# Common_slot2.net
KiCad netlist of a schematic drawn in EAGLE
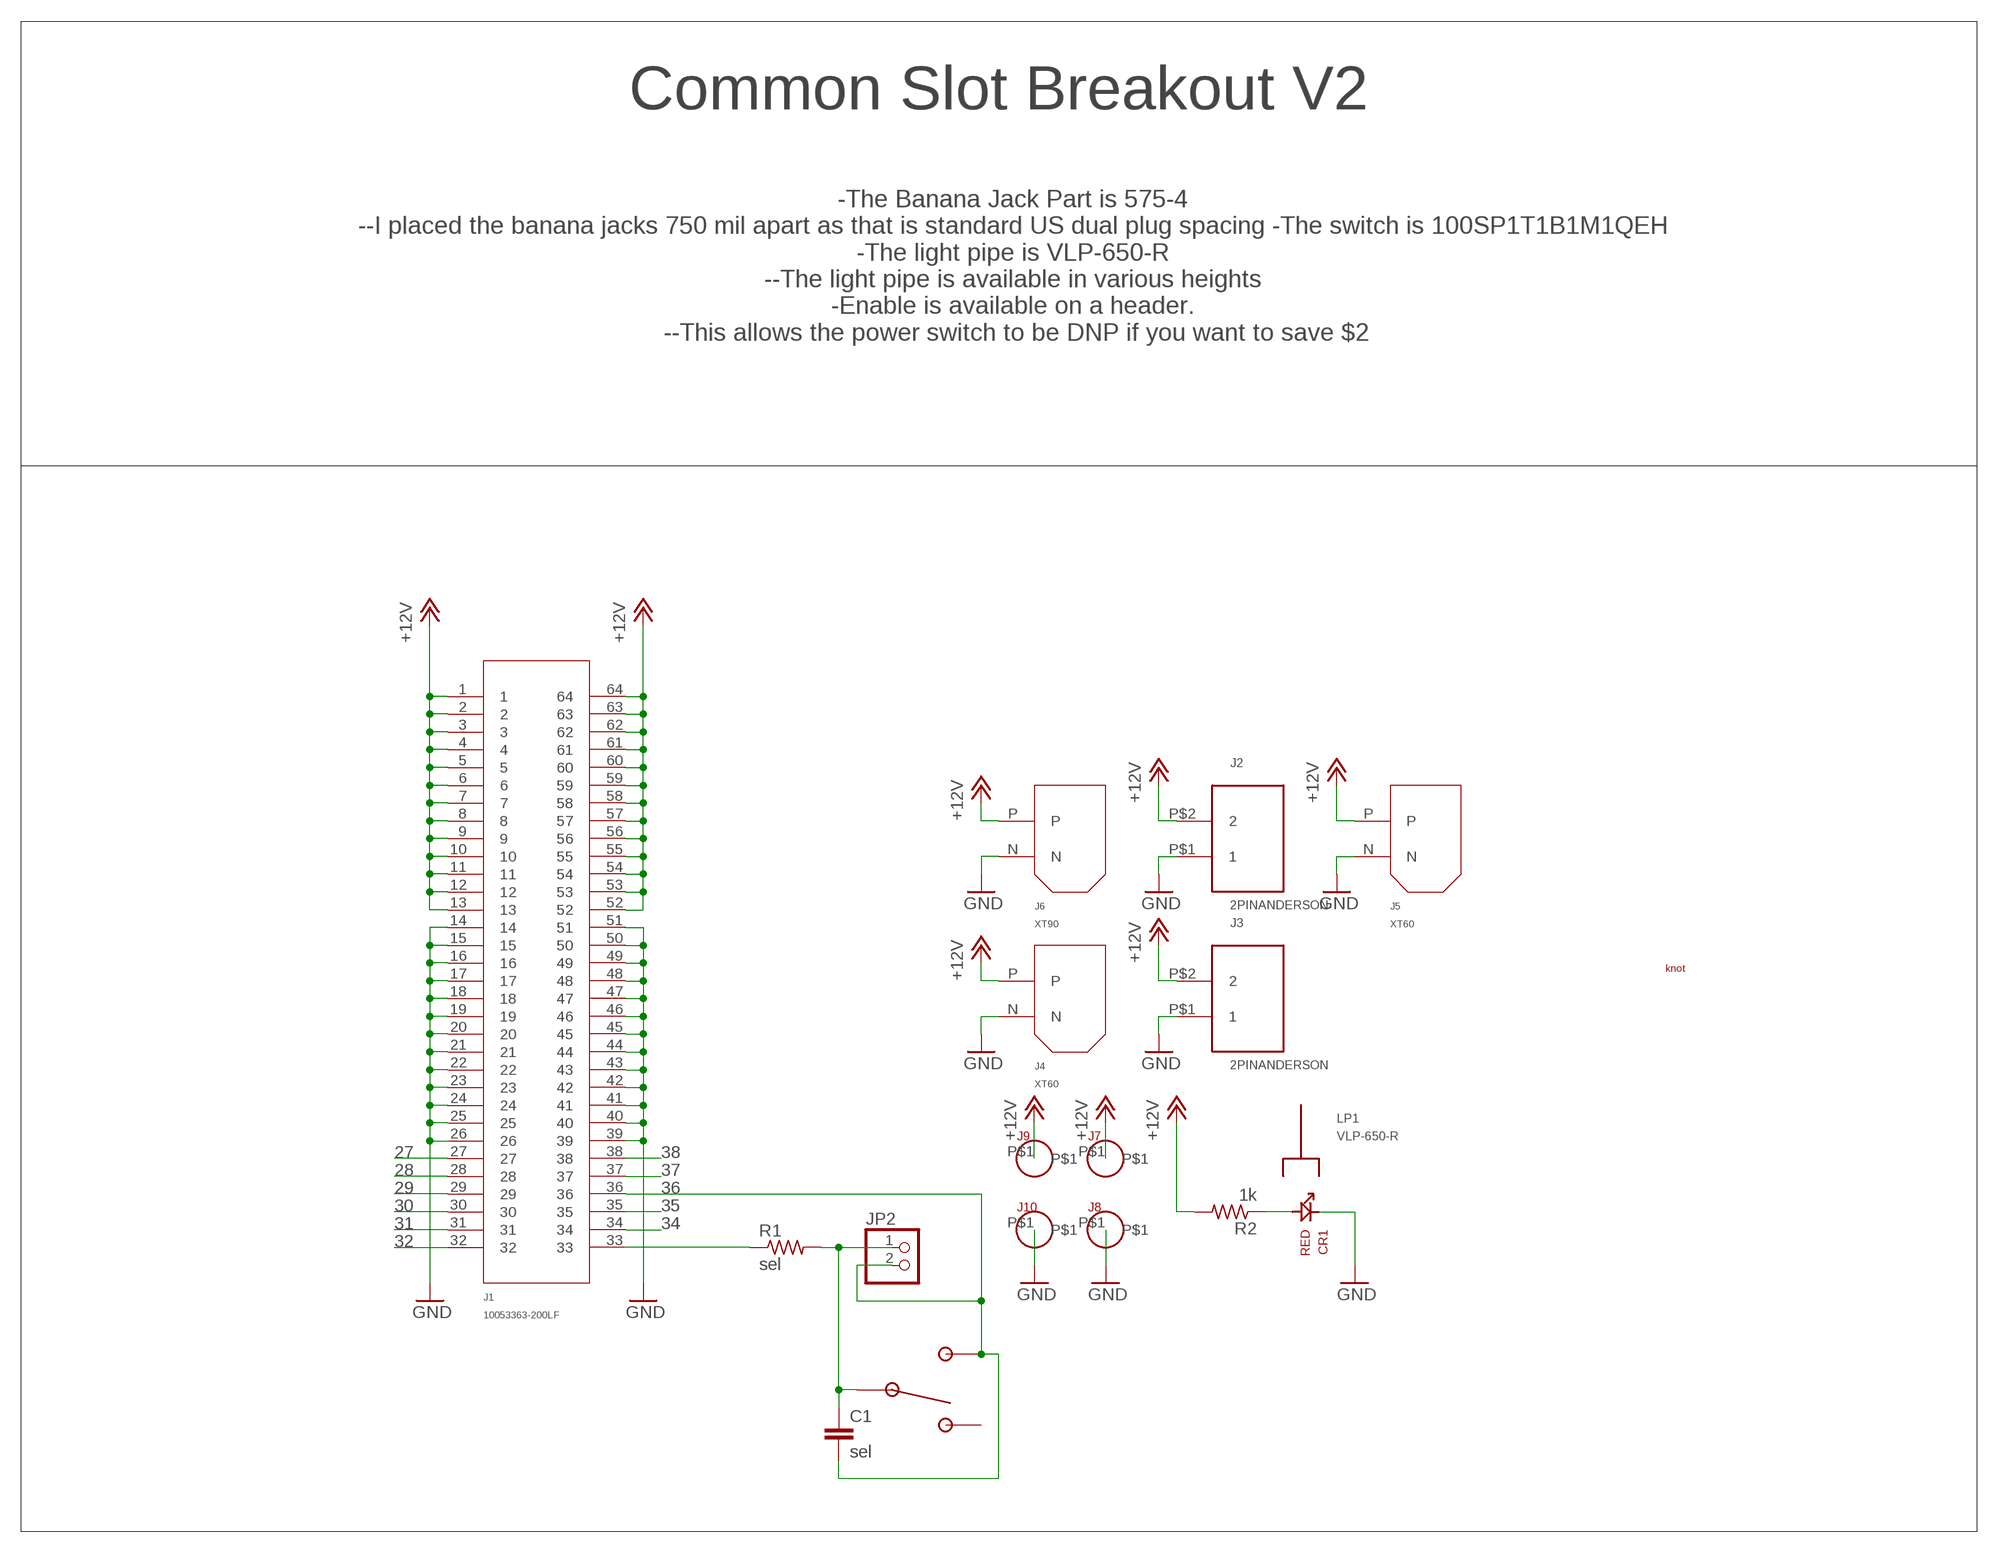
[diagram p0: schematic, sheet 1]

(export (version "E")
  (design (tool "Eeschema 10.0.6"))
  (components
    (comp (ref "C1")
      (value "sel")
      (footprint "eagle-import:0603")
      (libsource (lib "eagle-import") (part "0603_CAPACITOR"))
    )
    (comp (ref "CR1")
      (value "RED")
      (footprint "eagle-import:0603_DIODE")
      (fields (field (name "PARTNO") "732-4978-1-ND"))
      (libsource (lib "eagle-import") (part "150060RS75000"))
    )
    (comp (ref "J1")
      (value "10053363-200LF")
      (footprint "eagle-import:10053363-200LF")
      (fields (field (name "PARTNO") "609-2861-ND"))
      (libsource (lib "eagle-import") (part "10053363-200LF"))
    )
    (comp (ref "J2")
      (value "2PINANDERSON")
      (footprint "eagle-import:APP")
      (libsource (lib "eagle-import") (part "2PINANDERSON"))
    )
    (comp (ref "J3")
      (value "2PINANDERSON")
      (footprint "eagle-import:APP")
      (libsource (lib "eagle-import") (part "2PINANDERSON"))
    )
    (comp (ref "J4")
      (value "XT60")
      (footprint "eagle-import:XT60")
      (libsource (lib "eagle-import") (part "XT60"))
    )
    (comp (ref "J5")
      (value "XT60")
      (footprint "eagle-import:XT60")
      (libsource (lib "eagle-import") (part "XT60"))
    )
    (comp (ref "J6")
      (value "XT90")
      (footprint "eagle-import:XT90")
      (libsource (lib "eagle-import") (part "XT90"))
    )
    (comp (ref "J7")
      (value "BANANA")
      (footprint "eagle-import:BANANA")
      (fields (field (name "PARTNO") "36-575-4-ND"))
      (libsource (lib "eagle-import") (part "BANANA"))
    )
    (comp (ref "J8")
      (value "BANANA")
      (footprint "eagle-import:BANANA")
      (fields (field (name "PARTNO") "36-575-4-ND"))
      (libsource (lib "eagle-import") (part "BANANA"))
    )
    (comp (ref "J9")
      (value "BANANA")
      (footprint "eagle-import:BANANA")
      (fields (field (name "PARTNO") "36-575-4-ND"))
      (libsource (lib "eagle-import") (part "BANANA"))
    )
    (comp (ref "J10")
      (value "BANANA")
      (footprint "eagle-import:BANANA")
      (fields (field (name "PARTNO") "36-575-4-ND"))
      (libsource (lib "eagle-import") (part "BANANA"))
    )
    (comp (ref "JP2")
      (value "PINHD-1X2")
      (footprint "eagle-import:1X02")
      (libsource (lib "eagle-import") (part "PINHD-1X2"))
    )
    (comp (ref "LP1")
      (value "VLP-650-R")
      (footprint "eagle-import:VLP-XXX-R")
      (fields (field (name "PARTNO") "492-2537-ND"))
      (libsource (lib "eagle-import") (part "VLP-650-R"))
    )
    (comp (ref "R1")
      (value "sel")
      (footprint "eagle-import:0603")
      (libsource (lib "eagle-import") (part "0603_RESISTOR"))
    )
    (comp (ref "R2")
      (value "1k")
      (footprint "eagle-import:0603")
      (libsource (lib "eagle-import") (part "0603_RESISTOR"))
    )
    (comp (ref "SW1")
      (value "100SP1T1B1M1QEH")
      (footprint "eagle-import:100SP1T1B1M1QEH")
      (fields (field (name "PARTNO") "EG2350-ND"))
      (libsource (lib "eagle-import") (part "100SP1T1B1M1QEH"))
    )
    (comp (ref "U$1")
      (value "THIEF_FULL")
      (footprint "eagle-import:THIEF_KNOT")
      (fields (field (name "PARTNO") "NA"))
      (libsource (lib "eagle-import") (part "THIEF_FULL"))
    )
  )
  (nets
    (net (code "1") (name "+12V") (class "Default")
      (node (ref "J1") (pin "1") (pinfunction "1_1") (pintype "bidirectional"))
      (node (ref "J1") (pin "10") (pinfunction "10_10") (pintype "bidirectional"))
      (node (ref "J1") (pin "11") (pinfunction "11_11") (pintype "bidirectional"))
      (node (ref "J1") (pin "12") (pinfunction "12_12") (pintype "bidirectional"))
      (node (ref "J1") (pin "13") (pinfunction "13_13") (pintype "bidirectional"))
      (node (ref "J1") (pin "2") (pinfunction "2_2") (pintype "bidirectional"))
      (node (ref "J1") (pin "3") (pinfunction "3_3") (pintype "bidirectional"))
      (node (ref "J1") (pin "4") (pinfunction "4_4") (pintype "bidirectional"))
      (node (ref "J1") (pin "5") (pinfunction "5_5") (pintype "bidirectional"))
      (node (ref "J1") (pin "52") (pinfunction "52_52") (pintype "bidirectional"))
      (node (ref "J1") (pin "53") (pinfunction "53_53") (pintype "bidirectional"))
      (node (ref "J1") (pin "54") (pinfunction "54_54") (pintype "bidirectional"))
      (node (ref "J1") (pin "55") (pinfunction "55_55") (pintype "bidirectional"))
      (node (ref "J1") (pin "56") (pinfunction "56_56") (pintype "bidirectional"))
      (node (ref "J1") (pin "57") (pinfunction "57_57") (pintype "bidirectional"))
      (node (ref "J1") (pin "58") (pinfunction "58_58") (pintype "bidirectional"))
      (node (ref "J1") (pin "59") (pinfunction "59_59") (pintype "bidirectional"))
      (node (ref "J1") (pin "6") (pinfunction "6_6") (pintype "bidirectional"))
      (node (ref "J1") (pin "60") (pinfunction "60_60") (pintype "bidirectional"))
      (node (ref "J1") (pin "61") (pinfunction "61_61") (pintype "bidirectional"))
      (node (ref "J1") (pin "62") (pinfunction "62_62") (pintype "bidirectional"))
      (node (ref "J1") (pin "63") (pinfunction "63_63") (pintype "bidirectional"))
      (node (ref "J1") (pin "64") (pinfunction "64_64") (pintype "bidirectional"))
      (node (ref "J1") (pin "7") (pinfunction "7_7") (pintype "bidirectional"))
      (node (ref "J1") (pin "8") (pinfunction "8_8") (pintype "bidirectional"))
      (node (ref "J1") (pin "9") (pinfunction "9_9") (pintype "bidirectional"))
      (node (ref "J2") (pin "P$2") (pinfunction "2_P$2") (pintype "bidirectional"))
      (node (ref "J3") (pin "P$2") (pinfunction "2_P$2") (pintype "bidirectional"))
      (node (ref "J4") (pin "P") (pinfunction "P_P") (pintype "bidirectional"))
      (node (ref "J5") (pin "P") (pinfunction "P_P") (pintype "bidirectional"))
      (node (ref "J6") (pin "P") (pinfunction "P_P") (pintype "bidirectional"))
      (node (ref "J7") (pin "P$1") (pinfunction "P$1_P$1") (pintype "bidirectional"))
      (node (ref "J9") (pin "P$1") (pinfunction "P$1_P$1") (pintype "bidirectional"))
      (node (ref "R2") (pin "2") (pinfunction "2_2") (pintype "passive"))
    )
    (net (code "2") (name "/27") (class "Default")
      (node (ref "J1") (pin "27") (pinfunction "27_27") (pintype "bidirectional"))
    )
    (net (code "3") (name "/28") (class "Default")
      (node (ref "J1") (pin "28") (pinfunction "28_28") (pintype "bidirectional"))
    )
    (net (code "4") (name "/29") (class "Default")
      (node (ref "J1") (pin "29") (pinfunction "29_29") (pintype "bidirectional"))
    )
    (net (code "5") (name "/30") (class "Default")
      (node (ref "J1") (pin "30") (pinfunction "30_30") (pintype "bidirectional"))
    )
    (net (code "6") (name "/31") (class "Default")
      (node (ref "J1") (pin "31") (pinfunction "31_31") (pintype "bidirectional"))
    )
    (net (code "7") (name "/32") (class "Default")
      (node (ref "J1") (pin "32") (pinfunction "32_32") (pintype "bidirectional"))
    )
    (net (code "8") (name "/34") (class "Default")
      (node (ref "J1") (pin "34") (pinfunction "34_34") (pintype "bidirectional"))
    )
    (net (code "9") (name "/35") (class "Default")
      (node (ref "J1") (pin "35") (pinfunction "35_35") (pintype "bidirectional"))
    )
    (net (code "10") (name "/36") (class "Default")
      (node (ref "C1") (pin "2") (pinfunction "2_2") (pintype "passive"))
      (node (ref "J1") (pin "36") (pinfunction "36_36") (pintype "bidirectional"))
      (node (ref "JP2") (pin "2") (pinfunction "2_2") (pintype "passive"))
      (node (ref "SW1") (pin "2") (pinfunction "P$2_2") (pintype "bidirectional"))
    )
    (net (code "11") (name "/37") (class "Default")
      (node (ref "J1") (pin "37") (pinfunction "37_37") (pintype "bidirectional"))
    )
    (net (code "12") (name "/38") (class "Default")
      (node (ref "J1") (pin "38") (pinfunction "38_38") (pintype "bidirectional"))
    )
    (net (code "13") (name "GND") (class "Default")
      (node (ref "CR1") (pin "K") (pinfunction "K_K") (pintype "bidirectional"))
      (node (ref "J1") (pin "14") (pinfunction "14_14") (pintype "bidirectional"))
      (node (ref "J1") (pin "15") (pinfunction "15_15") (pintype "bidirectional"))
      (node (ref "J1") (pin "16") (pinfunction "16_16") (pintype "bidirectional"))
      (node (ref "J1") (pin "17") (pinfunction "17_17") (pintype "bidirectional"))
      (node (ref "J1") (pin "18") (pinfunction "18_18") (pintype "bidirectional"))
      (node (ref "J1") (pin "19") (pinfunction "19_19") (pintype "bidirectional"))
      (node (ref "J1") (pin "20") (pinfunction "20_20") (pintype "bidirectional"))
      (node (ref "J1") (pin "21") (pinfunction "21_21") (pintype "bidirectional"))
      (node (ref "J1") (pin "22") (pinfunction "22_22") (pintype "bidirectional"))
      (node (ref "J1") (pin "23") (pinfunction "23_23") (pintype "bidirectional"))
      (node (ref "J1") (pin "24") (pinfunction "24_24") (pintype "bidirectional"))
      (node (ref "J1") (pin "25") (pinfunction "25_25") (pintype "bidirectional"))
      (node (ref "J1") (pin "26") (pinfunction "26_26") (pintype "bidirectional"))
      (node (ref "J1") (pin "39") (pinfunction "39_39") (pintype "bidirectional"))
      (node (ref "J1") (pin "40") (pinfunction "40_40") (pintype "bidirectional"))
      (node (ref "J1") (pin "41") (pinfunction "41_41") (pintype "bidirectional"))
      (node (ref "J1") (pin "42") (pinfunction "42_42") (pintype "bidirectional"))
      (node (ref "J1") (pin "43") (pinfunction "43_43") (pintype "bidirectional"))
      (node (ref "J1") (pin "44") (pinfunction "44_44") (pintype "bidirectional"))
      (node (ref "J1") (pin "45") (pinfunction "45_45") (pintype "bidirectional"))
      (node (ref "J1") (pin "46") (pinfunction "46_46") (pintype "bidirectional"))
      (node (ref "J1") (pin "47") (pinfunction "47_47") (pintype "bidirectional"))
      (node (ref "J1") (pin "48") (pinfunction "48_48") (pintype "bidirectional"))
      (node (ref "J1") (pin "49") (pinfunction "49_49") (pintype "bidirectional"))
      (node (ref "J1") (pin "50") (pinfunction "50_50") (pintype "bidirectional"))
      (node (ref "J1") (pin "51") (pinfunction "51_51") (pintype "bidirectional"))
      (node (ref "J10") (pin "P$1") (pinfunction "P$1_P$1") (pintype "bidirectional"))
      (node (ref "J2") (pin "P$1") (pinfunction "1_P$1") (pintype "bidirectional"))
      (node (ref "J3") (pin "P$1") (pinfunction "1_P$1") (pintype "bidirectional"))
      (node (ref "J4") (pin "N") (pinfunction "N_N") (pintype "bidirectional"))
      (node (ref "J5") (pin "N") (pinfunction "N_N") (pintype "bidirectional"))
      (node (ref "J6") (pin "N") (pinfunction "N_N") (pintype "bidirectional"))
      (node (ref "J8") (pin "P$1") (pinfunction "P$1_P$1") (pintype "bidirectional"))
    )
    (net (code "14") (name "Net-(CR1-PadA)") (class "Default")
      (node (ref "CR1") (pin "A") (pinfunction "A_A") (pintype "bidirectional"))
      (node (ref "R2") (pin "1") (pinfunction "1_1") (pintype "passive"))
    )
    (net (code "15") (name "Net-(J1-Pad33)") (class "Default")
      (node (ref "J1") (pin "33") (pinfunction "33_33") (pintype "bidirectional"))
      (node (ref "R1") (pin "1") (pinfunction "1_1") (pintype "passive"))
    )
    (net (code "16") (name "Net-(SW1-COM)") (class "Default")
      (node (ref "C1") (pin "1") (pinfunction "1_1") (pintype "passive"))
      (node (ref "JP2") (pin "1") (pinfunction "1_1") (pintype "passive"))
      (node (ref "R1") (pin "2") (pinfunction "2_2") (pintype "passive"))
      (node (ref "SW1") (pin "C") (pinfunction "COM_C") (pintype "bidirectional"))
    )
    (net (code "17") (name "unconnected-(SW1-P$3-Pad1)") (class "Default")
      (node (ref "SW1") (pin "1") (pinfunction "P$3_1") (pintype "bidirectional"))
    )
  )
)
